# 02-bluetooth-V2_1.net
KiCad netlist of a schematic drawn in Altium Designer
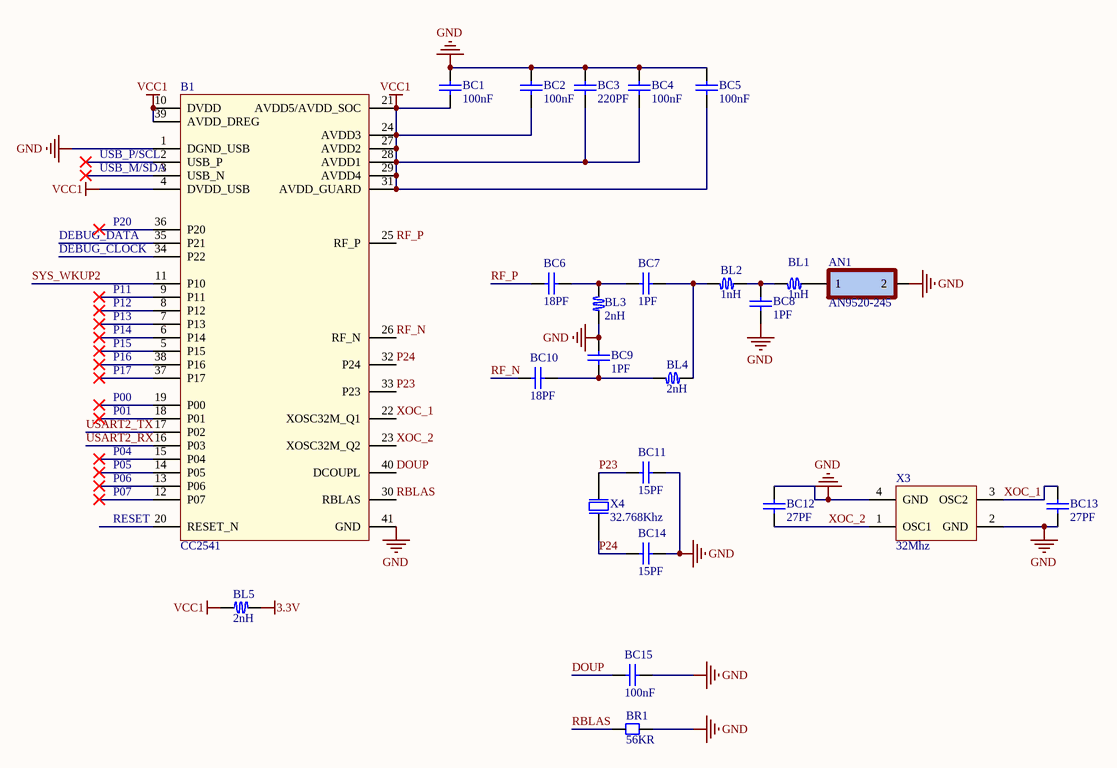
[diagram p0: 02-bluetooth-V2.1.SchDoc]

(export (version "E")
  (design (tool "Eeschema 10.0.6"))
  (components
    (comp (ref "AN1")
      (value "AN9520-245")
      (footprint "AN-5120")
      (description "2.4G全向天线 蓝牙天线 陶瓷贴片 WIFI内置")
      (libsource (lib "tianxiaohua_Schlib") (part "AN9520-245"))
    )
    (comp (ref "B1")
      (value "CC2541")
      (footprint "QFN40-CC254X")
      (description "低功耗蓝牙芯片")
      (libsource (lib "tianxiaohua_Schlib") (part "CC2541"))
    )
    (comp (ref "BC1")
      (value "100nF")
      (footprint "CC1005-0402")
      (description "0402封装电容")
      (fields (field (name "PUBLISHER") "Altium Limited"))
      (libsource (lib "tianxiaohua_Schlib") (part "Cap Chip 0402"))
    )
    (comp (ref "BC2")
      (value "100nF")
      (footprint "CC1005-0402")
      (description "0402封装电容")
      (fields (field (name "PUBLISHER") "Altium Limited"))
      (libsource (lib "tianxiaohua_Schlib") (part "Cap Chip 0402"))
    )
    (comp (ref "BC3")
      (value "220PF")
      (footprint "CC1005-0402")
      (description "0402封装电容")
      (fields (field (name "PUBLISHER") "Altium Limited"))
      (libsource (lib "tianxiaohua_Schlib") (part "Cap Chip 0402"))
    )
    (comp (ref "BC4")
      (value "100nF")
      (footprint "CC1005-0402")
      (description "0402封装电容")
      (fields (field (name "PUBLISHER") "Altium Limited"))
      (libsource (lib "tianxiaohua_Schlib") (part "Cap Chip 0402"))
    )
    (comp (ref "BC5")
      (value "100nF")
      (footprint "CC1005-0402")
      (description "0402封装电容")
      (fields (field (name "PUBLISHER") "Altium Limited"))
      (libsource (lib "tianxiaohua_Schlib") (part "Cap Chip 0402"))
    )
    (comp (ref "BC6")
      (value "18PF")
      (footprint "CC1005-0402")
      (description "0402封装电容")
      (fields (field (name "PUBLISHER") "Altium Limited"))
      (libsource (lib "tianxiaohua_Schlib") (part "Cap Chip 0402"))
    )
    (comp (ref "BC7")
      (value "1PF")
      (footprint "CC1005-0402")
      (description "0402封装电容")
      (fields (field (name "PUBLISHER") "Altium Limited"))
      (libsource (lib "tianxiaohua_Schlib") (part "Cap Chip 0402"))
    )
    (comp (ref "BC8")
      (value "1PF")
      (footprint "CC1005-0402")
      (description "0402封装电容")
      (fields (field (name "PUBLISHER") "Altium Limited"))
      (libsource (lib "tianxiaohua_Schlib") (part "Cap Chip 0402"))
    )
    (comp (ref "BC9")
      (value "1PF")
      (footprint "CC1005-0402")
      (description "0402封装电容")
      (fields (field (name "PUBLISHER") "Altium Limited"))
      (libsource (lib "tianxiaohua_Schlib") (part "Cap Chip 0402"))
    )
    (comp (ref "BC10")
      (value "18PF")
      (footprint "CC1005-0402")
      (description "0402封装电容")
      (fields (field (name "PUBLISHER") "Altium Limited"))
      (libsource (lib "tianxiaohua_Schlib") (part "Cap Chip 0402"))
    )
    (comp (ref "BC11")
      (value "15PF")
      (footprint "CC1005-0402")
      (description "0402封装电容")
      (fields (field (name "PUBLISHER") "Altium Limited"))
      (libsource (lib "tianxiaohua_Schlib") (part "Cap Chip 0402"))
    )
    (comp (ref "BC12")
      (value "27PF")
      (footprint "CC1005-0402")
      (description "0402封装电容")
      (fields (field (name "PUBLISHER") "Altium Limited"))
      (libsource (lib "tianxiaohua_Schlib") (part "Cap Chip 0402"))
    )
    (comp (ref "BC13")
      (value "27PF")
      (footprint "CC1005-0402")
      (description "0402封装电容")
      (fields (field (name "PUBLISHER") "Altium Limited"))
      (libsource (lib "tianxiaohua_Schlib") (part "Cap Chip 0402"))
    )
    (comp (ref "BC14")
      (value "15PF")
      (footprint "CC1005-0402")
      (description "0402封装电容")
      (fields (field (name "PUBLISHER") "Altium Limited"))
      (libsource (lib "tianxiaohua_Schlib") (part "Cap Chip 0402"))
    )
    (comp (ref "BC15")
      (value "100nF")
      (footprint "CC1005-0402")
      (description "0402封装电容")
      (fields (field (name "PUBLISHER") "Altium Limited"))
      (libsource (lib "tianxiaohua_Schlib") (part "Cap Chip 0402"))
    )
    (comp (ref "BL1")
      (value "1nH")
      (footprint "Inductor-0402")
      (description "0402封装的电感")
      (libsource (lib "tianxiaohua_Schlib") (part "Inductor-0402"))
    )
    (comp (ref "BL2")
      (value "1nH")
      (footprint "Inductor-0402")
      (description "0402封装的电感")
      (libsource (lib "tianxiaohua_Schlib") (part "Inductor-0402"))
    )
    (comp (ref "BL3")
      (value "2nH")
      (footprint "Inductor-0402")
      (description "0402封装的电感")
      (libsource (lib "") (part "Inductor-0402_1"))
    )
    (comp (ref "BL4")
      (value "2nH")
      (footprint "Inductor-0402")
      (description "0402封装的电感")
      (libsource (lib "tianxiaohua_Schlib") (part "Inductor-0402"))
    )
    (comp (ref "BL5")
      (value "2nH")
      (footprint "Inductor-0402")
      (description "0402封装的电感")
      (libsource (lib "tianxiaohua_Schlib") (part "Inductor-0402"))
    )
    (comp (ref "BR1")
      (value "56KR")
      (footprint "CR1005-0402")
      (description "贴片电阻")
      (libsource (lib "tianxiaohua_Schlib") (part "Chip resistor"))
    )
    (comp (ref "X3")
      (value "32Mhz")
      (footprint "XTAL-2016")
      (description "2016封装的晶振")
      (libsource (lib "tianxiaohua_Schlib") (part "XTAL 2016"))
    )
    (comp (ref "X4")
      (value "32.768Khz")
      (footprint "XTAL-2012")
      (description "2012封装的时钟晶振")
      (libsource (lib "tianxiaohua_Schlib") (part "XTAL 2012"))
    )
  )
  (nets
    (net (code "1") (name "/DEBUG_CLOCK") (class "Default")
      (node (ref "B1") (pin "34") (pinfunction "P22_34") (pintype "passive"))
    )
    (net (code "2") (name "/DEBUG_DATA") (class "Default")
      (node (ref "B1") (pin "35") (pinfunction "P21_35") (pintype "passive"))
    )
    (net (code "3") (name "/DOUP") (class "Default")
      (node (ref "B1") (pin "40") (pinfunction "DCOUPL_40") (pintype "passive"))
      (node (ref "BC15") (pin "2") (pinfunction "2_2") (pintype "passive"))
    )
    (net (code "4") (name "/P00") (class "Default")
      (node (ref "B1") (pin "19") (pinfunction "P00_19") (pintype "passive+no_connect"))
    )
    (net (code "5") (name "/P01") (class "Default")
      (node (ref "B1") (pin "18") (pinfunction "P01_18") (pintype "passive+no_connect"))
    )
    (net (code "6") (name "/P04") (class "Default")
      (node (ref "B1") (pin "15") (pinfunction "P04_15") (pintype "passive+no_connect"))
    )
    (net (code "7") (name "/P05") (class "Default")
      (node (ref "B1") (pin "14") (pinfunction "P05_14") (pintype "passive+no_connect"))
    )
    (net (code "8") (name "/P06") (class "Default")
      (node (ref "B1") (pin "13") (pinfunction "P06_13") (pintype "passive+no_connect"))
    )
    (net (code "9") (name "/P07") (class "Default")
      (node (ref "B1") (pin "12") (pinfunction "P07_12") (pintype "passive+no_connect"))
    )
    (net (code "10") (name "/P11") (class "Default")
      (node (ref "B1") (pin "9") (pinfunction "P11_9") (pintype "passive+no_connect"))
    )
    (net (code "11") (name "/P12") (class "Default")
      (node (ref "B1") (pin "8") (pinfunction "P12_8") (pintype "passive+no_connect"))
    )
    (net (code "12") (name "/P13") (class "Default")
      (node (ref "B1") (pin "7") (pinfunction "P13_7") (pintype "passive+no_connect"))
    )
    (net (code "13") (name "/P14") (class "Default")
      (node (ref "B1") (pin "6") (pinfunction "P14_6") (pintype "passive+no_connect"))
    )
    (net (code "14") (name "/P15") (class "Default")
      (node (ref "B1") (pin "5") (pinfunction "P15_5") (pintype "passive+no_connect"))
    )
    (net (code "15") (name "/P16") (class "Default")
      (node (ref "B1") (pin "38") (pinfunction "P16_38") (pintype "passive+no_connect"))
    )
    (net (code "16") (name "/P17") (class "Default")
      (node (ref "B1") (pin "37") (pinfunction "P17_37") (pintype "passive+no_connect"))
    )
    (net (code "17") (name "/P20") (class "Default")
      (node (ref "B1") (pin "36") (pinfunction "P20_36") (pintype "passive+no_connect"))
    )
    (net (code "18") (name "/P23") (class "Default")
      (node (ref "B1") (pin "33") (pinfunction "P23_33") (pintype "passive"))
      (node (ref "BC11") (pin "2") (pinfunction "2_2") (pintype "passive"))
      (node (ref "X4") (pin "2") (pinfunction "2_2") (pintype "passive"))
    )
    (net (code "19") (name "/P24") (class "Default")
      (node (ref "B1") (pin "32") (pinfunction "P24_32") (pintype "passive"))
      (node (ref "BC14") (pin "2") (pinfunction "2_2") (pintype "passive"))
      (node (ref "X4") (pin "1") (pinfunction "1_1") (pintype "passive"))
    )
    (net (code "20") (name "/RBLAS") (class "Default")
      (node (ref "B1") (pin "30") (pinfunction "RBLAS_30") (pintype "passive"))
      (node (ref "BR1") (pin "1") (pinfunction "1_1") (pintype "passive"))
    )
    (net (code "21") (name "/RESET") (class "Default")
      (node (ref "B1") (pin "20") (pinfunction "RESET_N_20") (pintype "passive"))
    )
    (net (code "22") (name "/RF_N") (class "Default")
      (node (ref "B1") (pin "26") (pinfunction "RF_N_26") (pintype "passive"))
      (node (ref "BC10") (pin "2") (pinfunction "2_2") (pintype "passive"))
    )
    (net (code "23") (name "/RF_P") (class "Default")
      (node (ref "B1") (pin "25") (pinfunction "RF_P_25") (pintype "passive"))
      (node (ref "BC6") (pin "2") (pinfunction "2_2") (pintype "passive"))
    )
    (net (code "24") (name "/SYS_WKUP2") (class "Default")
      (node (ref "B1") (pin "11") (pinfunction "P10_11") (pintype "passive"))
    )
    (net (code "25") (name "/USART2_RX") (class "Default")
      (node (ref "B1") (pin "16") (pinfunction "P03_16") (pintype "passive"))
    )
    (net (code "26") (name "/USART2_TX") (class "Default")
      (node (ref "B1") (pin "17") (pinfunction "P02_17") (pintype "passive"))
    )
    (net (code "27") (name "/USB_M{slash}SDA") (class "Default")
      (node (ref "B1") (pin "3") (pinfunction "USB_N_3") (pintype "passive+no_connect"))
    )
    (net (code "28") (name "/USB_P{slash}SCL") (class "Default")
      (node (ref "B1") (pin "2") (pinfunction "USB_P_2") (pintype "passive+no_connect"))
    )
    (net (code "29") (name "/XOC_1") (class "Default")
      (node (ref "B1") (pin "22") (pinfunction "XOSC32M_Q1_22") (pintype "passive"))
      (node (ref "BC13") (pin "1") (pinfunction "1_1") (pintype "passive"))
      (node (ref "X3") (pin "3") (pinfunction "OSC2_3") (pintype "passive"))
    )
    (net (code "30") (name "/XOC_2") (class "Default")
      (node (ref "B1") (pin "23") (pinfunction "XOSC32M_Q2_23") (pintype "passive"))
      (node (ref "BC12") (pin "2") (pinfunction "2_2") (pintype "passive"))
      (node (ref "X3") (pin "1") (pinfunction "OSC1_1") (pintype "passive"))
    )
    (net (code "31") (name "3.3V") (class "Default")
      (node (ref "BL5") (pin "2") (pinfunction "2_2") (pintype "passive"))
    )
    (net (code "32") (name "GND") (class "Default")
      (node (ref "AN1") (pin "2") (pinfunction "2_2") (pintype "passive"))
      (node (ref "B1") (pin "1") (pinfunction "DGND_USB_1") (pintype "passive"))
      (node (ref "B1") (pin "41") (pinfunction "GND_41") (pintype "passive"))
      (node (ref "BC1") (pin "2") (pinfunction "2_2") (pintype "passive"))
      (node (ref "BC11") (pin "1") (pinfunction "1_1") (pintype "passive"))
      (node (ref "BC12") (pin "1") (pinfunction "1_1") (pintype "passive"))
      (node (ref "BC13") (pin "2") (pinfunction "2_2") (pintype "passive"))
      (node (ref "BC14") (pin "1") (pinfunction "1_1") (pintype "passive"))
      (node (ref "BC15") (pin "1") (pinfunction "1_1") (pintype "passive"))
      (node (ref "BC2") (pin "2") (pinfunction "2_2") (pintype "passive"))
      (node (ref "BC3") (pin "2") (pinfunction "2_2") (pintype "passive"))
      (node (ref "BC4") (pin "2") (pinfunction "2_2") (pintype "passive"))
      (node (ref "BC5") (pin "2") (pinfunction "2_2") (pintype "passive"))
      (node (ref "BC8") (pin "2") (pinfunction "2_2") (pintype "passive"))
      (node (ref "BC9") (pin "2") (pinfunction "2_2") (pintype "passive"))
      (node (ref "BL3") (pin "1") (pinfunction "1_1") (pintype "passive"))
      (node (ref "BR1") (pin "2") (pinfunction "2_2") (pintype "passive"))
      (node (ref "X3") (pin "2") (pinfunction "GND_2") (pintype "passive"))
      (node (ref "X3") (pin "4") (pinfunction "GND_4") (pintype "passive"))
    )
    (net (code "33") (name "Net-(AN1-Pad1)") (class "Default")
      (node (ref "AN1") (pin "1") (pinfunction "1_1") (pintype "passive"))
      (node (ref "BL1") (pin "1") (pinfunction "1_1") (pintype "passive"))
    )
    (net (code "34") (name "Net-(BC6-Pad1)") (class "Default")
      (node (ref "BC6") (pin "1") (pinfunction "1_1") (pintype "passive"))
      (node (ref "BC7") (pin "2") (pinfunction "2_2") (pintype "passive"))
      (node (ref "BL3") (pin "2") (pinfunction "2_2") (pintype "passive"))
    )
    (net (code "35") (name "Net-(BC7-Pad1)") (class "Default")
      (node (ref "BC7") (pin "1") (pinfunction "1_1") (pintype "passive"))
      (node (ref "BL2") (pin "2") (pinfunction "2_2") (pintype "passive"))
      (node (ref "BL4") (pin "1") (pinfunction "1_1") (pintype "passive"))
    )
    (net (code "36") (name "Net-(BC8-Pad1)") (class "Default")
      (node (ref "BC8") (pin "1") (pinfunction "1_1") (pintype "passive"))
      (node (ref "BL1") (pin "2") (pinfunction "2_2") (pintype "passive"))
      (node (ref "BL2") (pin "1") (pinfunction "1_1") (pintype "passive"))
    )
    (net (code "37") (name "Net-(BC10-Pad1)") (class "Default")
      (node (ref "BC10") (pin "1") (pinfunction "1_1") (pintype "passive"))
      (node (ref "BC9") (pin "1") (pinfunction "1_1") (pintype "passive"))
      (node (ref "BL4") (pin "2") (pinfunction "2_2") (pintype "passive"))
    )
    (net (code "38") (name "VCC1") (class "Default")
      (node (ref "B1") (pin "10") (pinfunction "DVDD_10") (pintype "passive"))
      (node (ref "B1") (pin "21") (pinfunction "AVDD5/AVDD_SOC_21") (pintype "passive"))
      (node (ref "B1") (pin "24") (pinfunction "AVDD3_24") (pintype "passive"))
      (node (ref "B1") (pin "27") (pinfunction "AVDD2_27") (pintype "passive"))
      (node (ref "B1") (pin "28") (pinfunction "AVDD1_28") (pintype "passive"))
      (node (ref "B1") (pin "29") (pinfunction "AVDD4_29") (pintype "passive"))
      (node (ref "B1") (pin "31") (pinfunction "AVDD_GUARD_31") (pintype "passive"))
      (node (ref "B1") (pin "39") (pinfunction "AVDD_DREG_39") (pintype "passive"))
      (node (ref "B1") (pin "4") (pinfunction "DVDD_USB_4") (pintype "passive"))
      (node (ref "BC1") (pin "1") (pinfunction "1_1") (pintype "passive"))
      (node (ref "BC2") (pin "1") (pinfunction "1_1") (pintype "passive"))
      (node (ref "BC3") (pin "1") (pinfunction "1_1") (pintype "passive"))
      (node (ref "BC4") (pin "1") (pinfunction "1_1") (pintype "passive"))
      (node (ref "BC5") (pin "1") (pinfunction "1_1") (pintype "passive"))
      (node (ref "BL5") (pin "1") (pinfunction "1_1") (pintype "passive"))
    )
  )
)
